# Schemat1.net
KiCad netlist of a schematic drawn in EAGLE
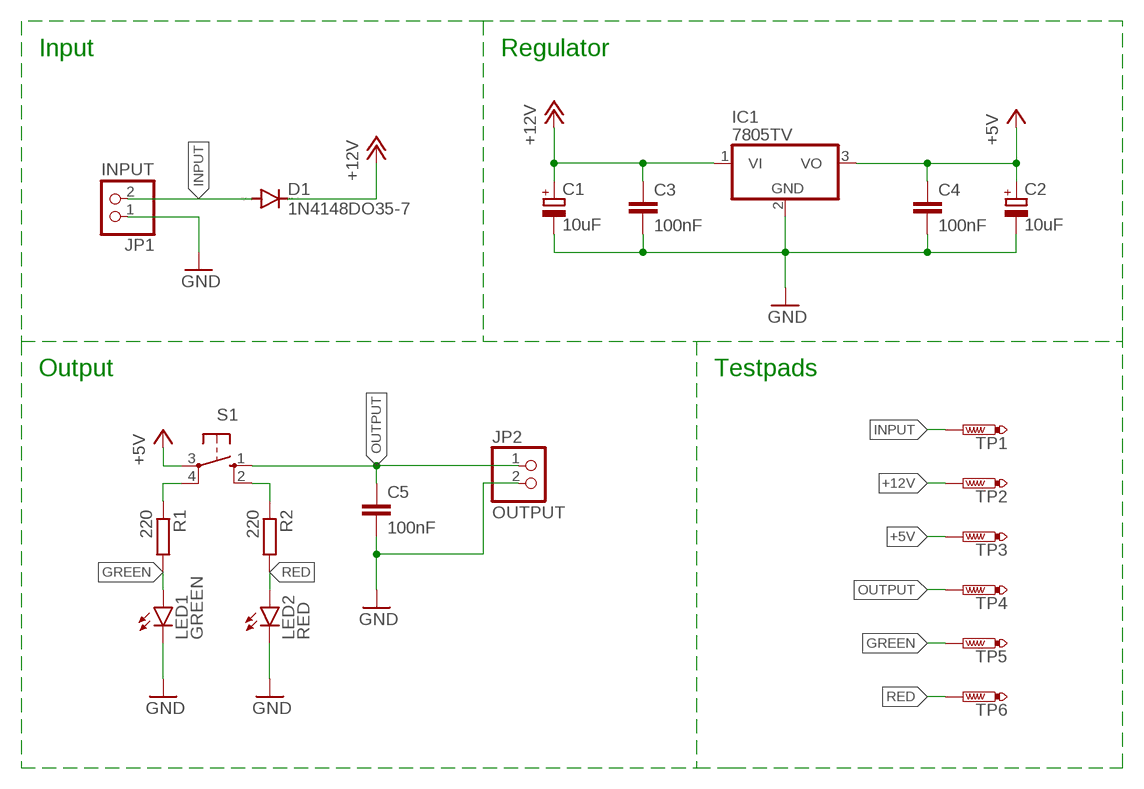
[diagram p0: schematic, sheet 1]

(export (version "E")
  (design (tool "Eeschema 10.0.6"))
  (components
    (comp (ref "C1")
      (value "10uF")
      (footprint "eagle-import:PANASONIC_D")
      (libsource (lib "eagle-import") (part "CPOL-EUD"))
    )
    (comp (ref "C2")
      (value "10uF")
      (footprint "eagle-import:PANASONIC_D")
      (libsource (lib "eagle-import") (part "CPOL-EUD"))
    )
    (comp (ref "C3")
      (value "100nF")
      (footprint "eagle-import:C025-025X050")
      (libsource (lib "eagle-import") (part "C-EU025-025X050"))
    )
    (comp (ref "C4")
      (value "100nF")
      (footprint "eagle-import:C025-025X050")
      (libsource (lib "eagle-import") (part "C-EU025-025X050"))
    )
    (comp (ref "C5")
      (value "100nF")
      (footprint "eagle-import:C025-025X050")
      (libsource (lib "eagle-import") (part "C-EU025-025X050"))
    )
    (comp (ref "D1")
      (value "1N4148DO35-7")
      (footprint "eagle-import:DO35-7")
      (libsource (lib "eagle-import") (part "1N4148DO35-7"))
    )
    (comp (ref "IC1")
      (value "7805TV")
      (footprint "eagle-import:TO220V")
      (libsource (lib "eagle-import") (part "78TV05"))
    )
    (comp (ref "JP1")
      (value "INPUT")
      (footprint "eagle-import:1X02")
      (libsource (lib "eagle-import") (part "PINHD-1X2"))
    )
    (comp (ref "JP2")
      (value "OUTPUT")
      (footprint "eagle-import:1X02")
      (libsource (lib "eagle-import") (part "PINHD-1X2"))
    )
    (comp (ref "LED1")
      (value "GREEN")
      (footprint "eagle-import:LED5MM")
      (libsource (lib "eagle-import") (part "LED5MM"))
    )
    (comp (ref "LED2")
      (value "RED")
      (footprint "eagle-import:LED5MM")
      (libsource (lib "eagle-import") (part "LED5MM"))
    )
    (comp (ref "R1")
      (value "220")
      (footprint "eagle-import:0207_10")
      (libsource (lib "eagle-import") (part "R-EU_0207/10"))
    )
    (comp (ref "R2")
      (value "220")
      (footprint "eagle-import:0207_10")
      (libsource (lib "eagle-import") (part "R-EU_0207/10"))
    )
    (comp (ref "S1")
      (value "10-XX")
      (footprint "eagle-import:B3F-10XX")
      (fields (field (name "MPN") "B3F-1000"))
      (libsource (lib "eagle-import") (part "10-XX"))
    )
    (comp (ref "TP1")
      (value "PTR1TP15R")
      (footprint "eagle-import:TP15R")
      (libsource (lib "eagle-import") (part "PTR1TP15R"))
    )
    (comp (ref "TP2")
      (value "PTR1TP15R")
      (footprint "eagle-import:TP15R")
      (libsource (lib "eagle-import") (part "PTR1TP15R"))
    )
    (comp (ref "TP3")
      (value "PTR1TP15R")
      (footprint "eagle-import:TP15R")
      (libsource (lib "eagle-import") (part "PTR1TP15R"))
    )
    (comp (ref "TP4")
      (value "PTR1TP15R")
      (footprint "eagle-import:TP15R")
      (libsource (lib "eagle-import") (part "PTR1TP15R"))
    )
    (comp (ref "TP5")
      (value "PTR1TP15R")
      (footprint "eagle-import:TP15R")
      (libsource (lib "eagle-import") (part "PTR1TP15R"))
    )
    (comp (ref "TP6")
      (value "PTR1TP15R")
      (footprint "eagle-import:TP15R")
      (libsource (lib "eagle-import") (part "PTR1TP15R"))
    )
  )
  (nets
    (net (code "1") (name "+5V") (class "Default")
      (node (ref "C2") (pin "+") (pinfunction "+_+") (pintype "passive"))
      (node (ref "C4") (pin "1") (pinfunction "1_1") (pintype "passive"))
      (node (ref "IC1") (pin "3") (pinfunction "VO_3") (pintype "passive"))
      (node (ref "S1") (pin "3") (pinfunction "P_3") (pintype "passive"))
      (node (ref "TP3") (pin "TP") (pinfunction "TP_TP") (pintype "input"))
    )
    (net (code "2") (name "+12V") (class "Default")
      (node (ref "C1") (pin "+") (pinfunction "+_+") (pintype "passive"))
      (node (ref "C3") (pin "1") (pinfunction "1_1") (pintype "passive"))
      (node (ref "D1") (pin "C") (pinfunction "C_C") (pintype "passive"))
      (node (ref "IC1") (pin "1") (pinfunction "VI_1") (pintype "input"))
      (node (ref "TP2") (pin "TP") (pinfunction "TP_TP") (pintype "input"))
    )
    (net (code "3") (name "GND") (class "Default")
      (node (ref "C1") (pin "-") (pinfunction "-_-") (pintype "passive"))
      (node (ref "C2") (pin "-") (pinfunction "-_-") (pintype "passive"))
      (node (ref "C3") (pin "2") (pinfunction "2_2") (pintype "passive"))
      (node (ref "C4") (pin "2") (pinfunction "2_2") (pintype "passive"))
      (node (ref "C5") (pin "2") (pinfunction "2_2") (pintype "passive"))
      (node (ref "IC1") (pin "2") (pinfunction "GND_2") (pintype "passive"))
      (node (ref "JP1") (pin "1") (pinfunction "1_1") (pintype "passive"))
      (node (ref "JP2") (pin "2") (pinfunction "2_2") (pintype "passive"))
      (node (ref "LED1") (pin "K") (pinfunction "C_K") (pintype "passive"))
      (node (ref "LED2") (pin "K") (pinfunction "C_K") (pintype "passive"))
    )
    (net (code "4") (name "GREEN") (class "Default")
      (node (ref "LED1") (pin "A") (pinfunction "A_A") (pintype "passive"))
      (node (ref "R1") (pin "2") (pinfunction "2_2") (pintype "passive"))
      (node (ref "TP5") (pin "TP") (pinfunction "TP_TP") (pintype "input"))
    )
    (net (code "5") (name "INPUT") (class "Default")
      (node (ref "D1") (pin "A") (pinfunction "A_A") (pintype "passive"))
      (node (ref "JP1") (pin "2") (pinfunction "2_2") (pintype "passive"))
      (node (ref "TP1") (pin "TP") (pinfunction "TP_TP") (pintype "input"))
    )
    (net (code "6") (name "Net-(S1-P1)") (class "Default")
      (node (ref "R1") (pin "1") (pinfunction "1_1") (pintype "passive"))
      (node (ref "S1") (pin "4") (pinfunction "P1_4") (pintype "passive"))
    )
    (net (code "7") (name "Net-(S1-S1)") (class "Default")
      (node (ref "R2") (pin "1") (pinfunction "1_1") (pintype "passive"))
      (node (ref "S1") (pin "2") (pinfunction "S1_2") (pintype "passive"))
    )
    (net (code "8") (name "OUTPUT") (class "Default")
      (node (ref "C5") (pin "1") (pinfunction "1_1") (pintype "passive"))
      (node (ref "JP2") (pin "1") (pinfunction "1_1") (pintype "passive"))
      (node (ref "S1") (pin "1") (pinfunction "S_1") (pintype "passive"))
      (node (ref "TP4") (pin "TP") (pinfunction "TP_TP") (pintype "input"))
    )
    (net (code "9") (name "RED") (class "Default")
      (node (ref "LED2") (pin "A") (pinfunction "A_A") (pintype "passive"))
      (node (ref "R2") (pin "2") (pinfunction "2_2") (pintype "passive"))
      (node (ref "TP6") (pin "TP") (pinfunction "TP_TP") (pintype "input"))
    )
  )
)
